# PowerBricksBoard1.net
KiCad netlist of a schematic drawn in EAGLE
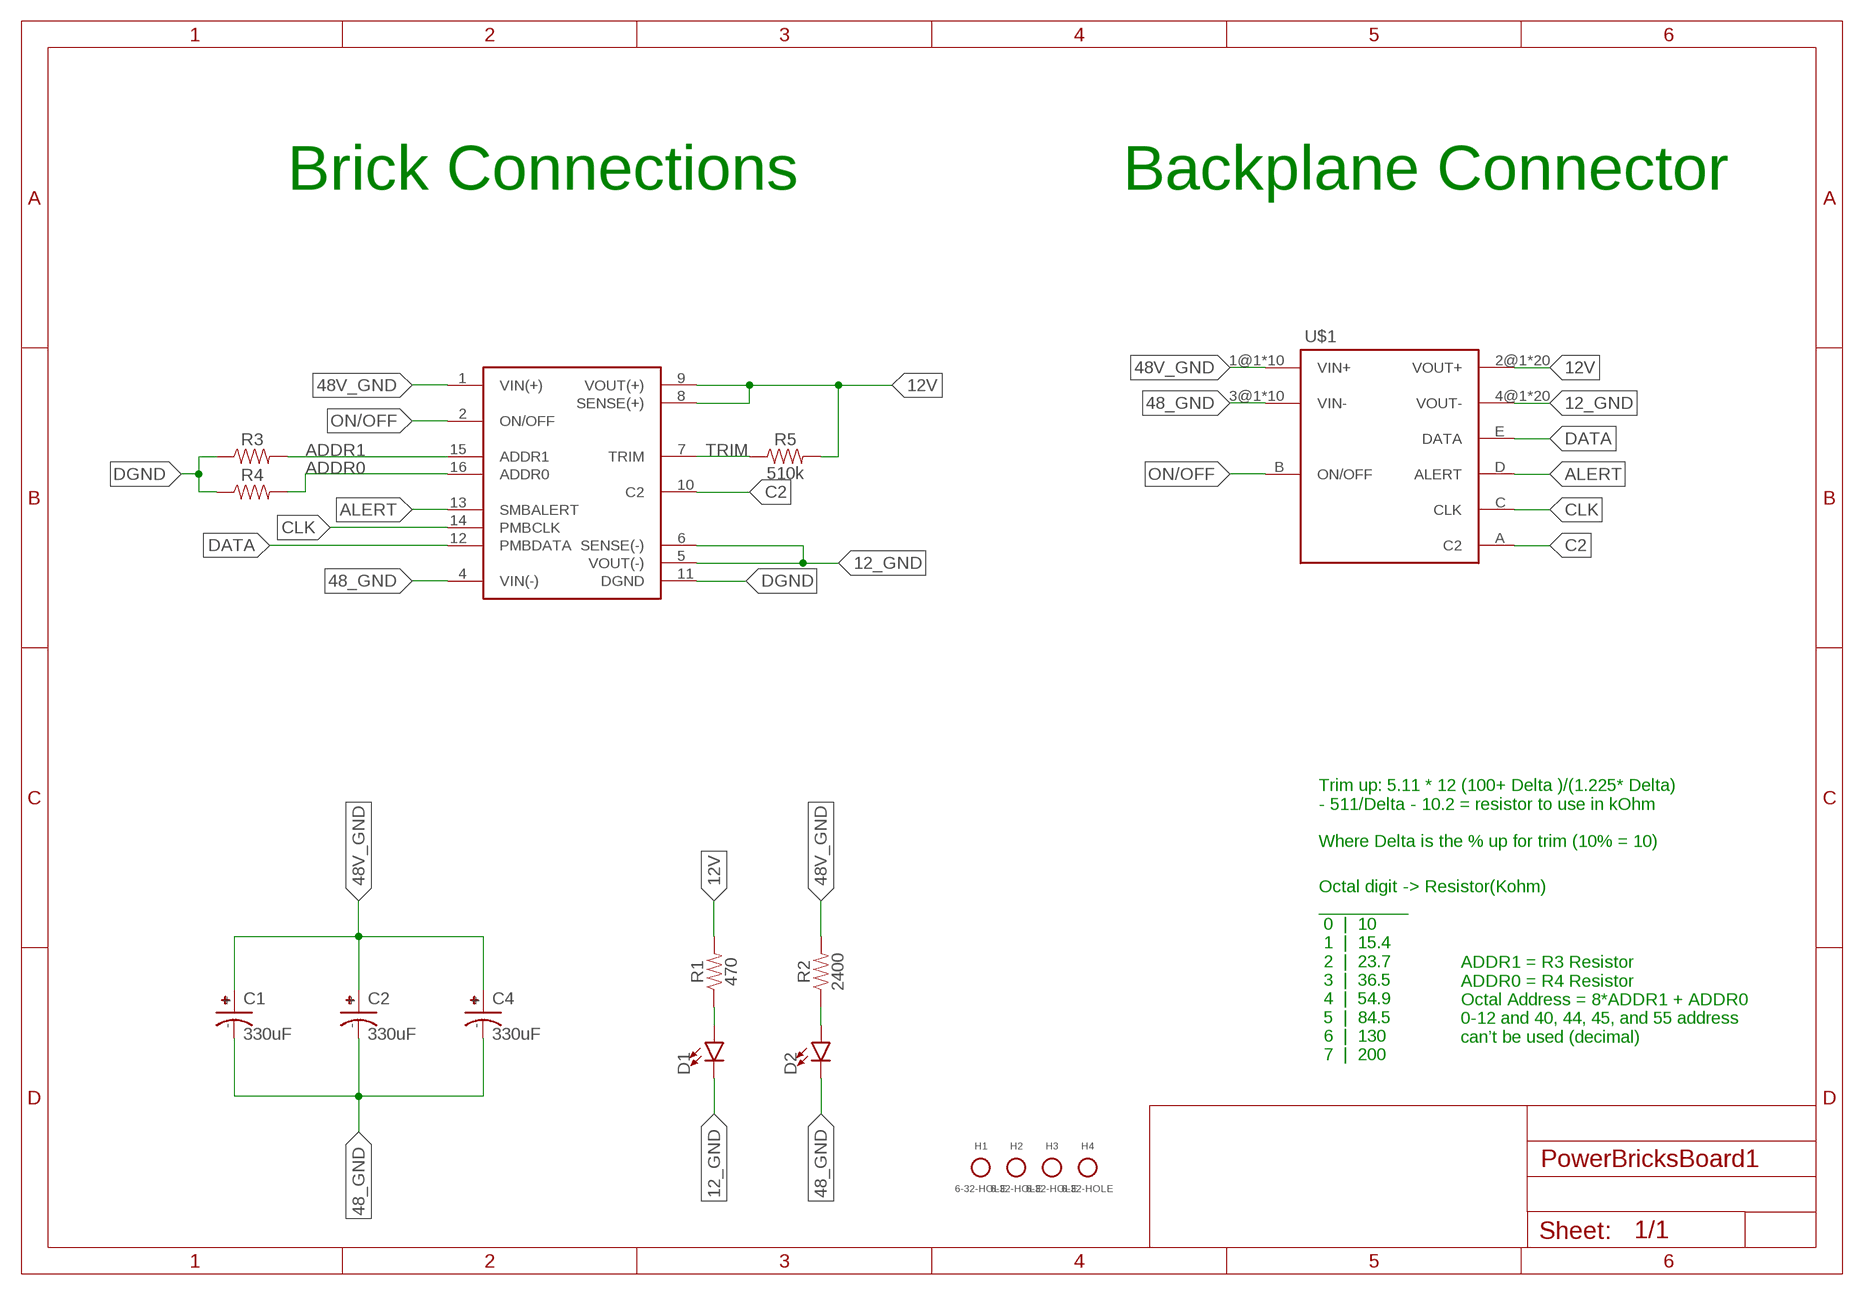
[diagram p0: schematic, sheet 1]

(export (version "E")
  (design (tool "Eeschema 10.0.6"))
  (components
    (comp (ref "C1")
      (value "330uF")
      (footprint "eagle-import:CAPAE1030X1050N")
      (fields
        (field (name "ARROW_PART_NUMBER") "UCM1H331MNL1GS")
        (field (name "MOUSER_PART_NUMBER") "647-UCM1H331MNL1GS")
      )
      (libsource (lib "eagle-import") (part "UCM1H331MNL1GS"))
    )
    (comp (ref "C2")
      (value "330uF")
      (footprint "eagle-import:CAPAE1030X1050N")
      (fields
        (field (name "ARROW_PART_NUMBER") "UCM1H331MNL1GS")
        (field (name "MOUSER_PART_NUMBER") "647-UCM1H331MNL1GS")
      )
      (libsource (lib "eagle-import") (part "UCM1H331MNL1GS"))
    )
    (comp (ref "C4")
      (value "330uF")
      (footprint "eagle-import:CAPAE1030X1050N")
      (fields
        (field (name "ARROW_PART_NUMBER") "UCM1H331MNL1GS")
        (field (name "MOUSER_PART_NUMBER") "647-UCM1H331MNL1GS")
      )
      (libsource (lib "eagle-import") (part "UCM1H331MNL1GS"))
    )
    (comp (ref "D1")
      (value "LED0603")
      (footprint "eagle-import:LED-0603")
      (libsource (lib "eagle-import") (part "LED0603"))
    )
    (comp (ref "D2")
      (value "LED0603")
      (footprint "eagle-import:LED-0603")
      (libsource (lib "eagle-import") (part "LED0603"))
    )
    (comp (ref "H1")
      (value "6-32-HOLE")
      (footprint "eagle-import:6-32-HOLE")
      (libsource (lib "eagle-import") (part "6-32-HOLE"))
    )
    (comp (ref "H2")
      (value "6-32-HOLE")
      (footprint "eagle-import:6-32-HOLE")
      (libsource (lib "eagle-import") (part "6-32-HOLE"))
    )
    (comp (ref "H3")
      (value "6-32-HOLE")
      (footprint "eagle-import:6-32-HOLE")
      (libsource (lib "eagle-import") (part "6-32-HOLE"))
    )
    (comp (ref "H4")
      (value "6-32-HOLE")
      (footprint "eagle-import:6-32-HOLE")
      (libsource (lib "eagle-import") (part "6-32-HOLE"))
    )
    (comp (ref "R1")
      (value "470")
      (footprint "eagle-import:0603")
      (libsource (lib "eagle-import") (part "RESISTOR0603"))
    )
    (comp (ref "R2")
      (value "2400")
      (footprint "eagle-import:0603")
      (libsource (lib "eagle-import") (part "RESISTOR0603"))
    )
    (comp (ref "R3")
      (value "RESISTOR0603")
      (footprint "eagle-import:0603")
      (libsource (lib "eagle-import") (part "RESISTOR0603"))
    )
    (comp (ref "R4")
      (value "RESISTOR0603")
      (footprint "eagle-import:0603")
      (libsource (lib "eagle-import") (part "RESISTOR0603"))
    )
    (comp (ref "R5")
      (value "510k")
      (footprint "eagle-import:0603")
      (libsource (lib "eagle-import") (part "RESISTOR0603"))
    )
    (comp (ref "U$1")
      (value "BRICK2DIST")
      (footprint "eagle-import:BRICK2DIST_D2")
      (libsource (lib "eagle-import") (part "BRICK2DIST"))
    )
    (comp (ref "U$2")
      (value "Q48SC12050NRDH")
      (footprint "eagle-import:Q48SC12050NRDH")
      (libsource (lib "eagle-import") (part "Q48SC12050NRDH"))
    )
  )
  (nets
    (net (code "1") (name "/ADDR0") (class "Default")
      (node (ref "R4") (pin "2") (pinfunction "2_2") (pintype "passive"))
      (node (ref "U$2") (pin "16") (pinfunction "ADDR0_16") (pintype "bidirectional"))
    )
    (net (code "2") (name "/ADDR1") (class "Default")
      (node (ref "R3") (pin "2") (pinfunction "2_2") (pintype "passive"))
      (node (ref "U$2") (pin "15") (pinfunction "ADDR1_15") (pintype "bidirectional"))
    )
    (net (code "3") (name "/TRIM") (class "Default")
      (node (ref "R5") (pin "1") (pinfunction "1_1") (pintype "passive"))
      (node (ref "U$2") (pin "7") (pinfunction "TRIM_7") (pintype "bidirectional"))
    )
    (net (code "4") (name "12V") (class "Default")
      (node (ref "R1") (pin "2") (pinfunction "2_2") (pintype "passive"))
      (node (ref "R5") (pin "2") (pinfunction "2_2") (pintype "passive"))
      (node (ref "U$1") (pin "2@1") (pinfunction "VOUT+_2@1") (pintype "bidirectional"))
      (node (ref "U$1") (pin "2@10") (pinfunction "VOUT+_2@10") (pintype "bidirectional"))
      (node (ref "U$1") (pin "2@11") (pinfunction "VOUT+_2@11") (pintype "bidirectional"))
      (node (ref "U$1") (pin "2@12") (pinfunction "VOUT+_2@12") (pintype "bidirectional"))
      (node (ref "U$1") (pin "2@13") (pinfunction "VOUT+_2@13") (pintype "bidirectional"))
      (node (ref "U$1") (pin "2@14") (pinfunction "VOUT+_2@14") (pintype "bidirectional"))
      (node (ref "U$1") (pin "2@15") (pinfunction "VOUT+_2@15") (pintype "bidirectional"))
      (node (ref "U$1") (pin "2@16") (pinfunction "VOUT+_2@16") (pintype "bidirectional"))
      (node (ref "U$1") (pin "2@17") (pinfunction "VOUT+_2@17") (pintype "bidirectional"))
      (node (ref "U$1") (pin "2@18") (pinfunction "VOUT+_2@18") (pintype "bidirectional"))
      (node (ref "U$1") (pin "2@19") (pinfunction "VOUT+_2@19") (pintype "bidirectional"))
      (node (ref "U$1") (pin "2@2") (pinfunction "VOUT+_2@2") (pintype "bidirectional"))
      (node (ref "U$1") (pin "2@20") (pinfunction "VOUT+_2@20") (pintype "bidirectional"))
      (node (ref "U$1") (pin "2@3") (pinfunction "VOUT+_2@3") (pintype "bidirectional"))
      (node (ref "U$1") (pin "2@4") (pinfunction "VOUT+_2@4") (pintype "bidirectional"))
      (node (ref "U$1") (pin "2@5") (pinfunction "VOUT+_2@5") (pintype "bidirectional"))
      (node (ref "U$1") (pin "2@6") (pinfunction "VOUT+_2@6") (pintype "bidirectional"))
      (node (ref "U$1") (pin "2@7") (pinfunction "VOUT+_2@7") (pintype "bidirectional"))
      (node (ref "U$1") (pin "2@8") (pinfunction "VOUT+_2@8") (pintype "bidirectional"))
      (node (ref "U$1") (pin "2@9") (pinfunction "VOUT+_2@9") (pintype "bidirectional"))
      (node (ref "U$2") (pin "8") (pinfunction "SENSE(+)_8") (pintype "bidirectional"))
      (node (ref "U$2") (pin "9") (pinfunction "VOUT(+)_9") (pintype "bidirectional"))
    )
    (net (code "5") (name "12_GND") (class "Default")
      (node (ref "D1") (pin "C") (pinfunction "C_C") (pintype "passive"))
      (node (ref "U$1") (pin "4@1") (pinfunction "VOUT-_4@1") (pintype "bidirectional"))
      (node (ref "U$1") (pin "4@10") (pinfunction "VOUT-_4@10") (pintype "bidirectional"))
      (node (ref "U$1") (pin "4@11") (pinfunction "VOUT-_4@11") (pintype "bidirectional"))
      (node (ref "U$1") (pin "4@12") (pinfunction "VOUT-_4@12") (pintype "bidirectional"))
      (node (ref "U$1") (pin "4@13") (pinfunction "VOUT-_4@13") (pintype "bidirectional"))
      (node (ref "U$1") (pin "4@14") (pinfunction "VOUT-_4@14") (pintype "bidirectional"))
      (node (ref "U$1") (pin "4@15") (pinfunction "VOUT-_4@15") (pintype "bidirectional"))
      (node (ref "U$1") (pin "4@16") (pinfunction "VOUT-_4@16") (pintype "bidirectional"))
      (node (ref "U$1") (pin "4@17") (pinfunction "VOUT-_4@17") (pintype "bidirectional"))
      (node (ref "U$1") (pin "4@18") (pinfunction "VOUT-_4@18") (pintype "bidirectional"))
      (node (ref "U$1") (pin "4@19") (pinfunction "VOUT-_4@19") (pintype "bidirectional"))
      (node (ref "U$1") (pin "4@2") (pinfunction "VOUT-_4@2") (pintype "bidirectional"))
      (node (ref "U$1") (pin "4@20") (pinfunction "VOUT-_4@20") (pintype "bidirectional"))
      (node (ref "U$1") (pin "4@3") (pinfunction "VOUT-_4@3") (pintype "bidirectional"))
      (node (ref "U$1") (pin "4@4") (pinfunction "VOUT-_4@4") (pintype "bidirectional"))
      (node (ref "U$1") (pin "4@5") (pinfunction "VOUT-_4@5") (pintype "bidirectional"))
      (node (ref "U$1") (pin "4@6") (pinfunction "VOUT-_4@6") (pintype "bidirectional"))
      (node (ref "U$1") (pin "4@7") (pinfunction "VOUT-_4@7") (pintype "bidirectional"))
      (node (ref "U$1") (pin "4@8") (pinfunction "VOUT-_4@8") (pintype "bidirectional"))
      (node (ref "U$1") (pin "4@9") (pinfunction "VOUT-_4@9") (pintype "bidirectional"))
      (node (ref "U$2") (pin "5") (pinfunction "VOUT(-)_5") (pintype "bidirectional"))
      (node (ref "U$2") (pin "6") (pinfunction "SENSE(-)_6") (pintype "bidirectional"))
    )
    (net (code "6") (name "48V_GND") (class "Default")
      (node (ref "C1") (pin "+") (pinfunction "+_+") (pintype "bidirectional"))
      (node (ref "C2") (pin "+") (pinfunction "+_+") (pintype "bidirectional"))
      (node (ref "C4") (pin "+") (pinfunction "+_+") (pintype "bidirectional"))
      (node (ref "R2") (pin "2") (pinfunction "2_2") (pintype "passive"))
      (node (ref "U$1") (pin "1@1") (pinfunction "VIN+_1@1") (pintype "bidirectional"))
      (node (ref "U$1") (pin "1@10") (pinfunction "VIN+_1@10") (pintype "bidirectional"))
      (node (ref "U$1") (pin "1@2") (pinfunction "VIN+_1@2") (pintype "bidirectional"))
      (node (ref "U$1") (pin "1@3") (pinfunction "VIN+_1@3") (pintype "bidirectional"))
      (node (ref "U$1") (pin "1@4") (pinfunction "VIN+_1@4") (pintype "bidirectional"))
      (node (ref "U$1") (pin "1@5") (pinfunction "VIN+_1@5") (pintype "bidirectional"))
      (node (ref "U$1") (pin "1@6") (pinfunction "VIN+_1@6") (pintype "bidirectional"))
      (node (ref "U$1") (pin "1@7") (pinfunction "VIN+_1@7") (pintype "bidirectional"))
      (node (ref "U$1") (pin "1@8") (pinfunction "VIN+_1@8") (pintype "bidirectional"))
      (node (ref "U$1") (pin "1@9") (pinfunction "VIN+_1@9") (pintype "bidirectional"))
      (node (ref "U$2") (pin "1") (pinfunction "VIN(+)_1") (pintype "bidirectional"))
    )
    (net (code "7") (name "48_GND") (class "Default")
      (node (ref "C1") (pin "-") (pinfunction "-_-") (pintype "bidirectional"))
      (node (ref "C2") (pin "-") (pinfunction "-_-") (pintype "bidirectional"))
      (node (ref "C4") (pin "-") (pinfunction "-_-") (pintype "bidirectional"))
      (node (ref "D2") (pin "C") (pinfunction "C_C") (pintype "passive"))
      (node (ref "U$1") (pin "3@1") (pinfunction "VIN-_3@1") (pintype "bidirectional"))
      (node (ref "U$1") (pin "3@10") (pinfunction "VIN-_3@10") (pintype "bidirectional"))
      (node (ref "U$1") (pin "3@2") (pinfunction "VIN-_3@2") (pintype "bidirectional"))
      (node (ref "U$1") (pin "3@3") (pinfunction "VIN-_3@3") (pintype "bidirectional"))
      (node (ref "U$1") (pin "3@4") (pinfunction "VIN-_3@4") (pintype "bidirectional"))
      (node (ref "U$1") (pin "3@5") (pinfunction "VIN-_3@5") (pintype "bidirectional"))
      (node (ref "U$1") (pin "3@6") (pinfunction "VIN-_3@6") (pintype "bidirectional"))
      (node (ref "U$1") (pin "3@7") (pinfunction "VIN-_3@7") (pintype "bidirectional"))
      (node (ref "U$1") (pin "3@8") (pinfunction "VIN-_3@8") (pintype "bidirectional"))
      (node (ref "U$1") (pin "3@9") (pinfunction "VIN-_3@9") (pintype "bidirectional"))
      (node (ref "U$2") (pin "4") (pinfunction "VIN(-)_4") (pintype "bidirectional"))
    )
    (net (code "8") (name "ALERT") (class "Default")
      (node (ref "U$1") (pin "D") (pinfunction "ALERT_D") (pintype "bidirectional"))
      (node (ref "U$2") (pin "13") (pinfunction "SMBALERT_13") (pintype "bidirectional"))
    )
    (net (code "9") (name "C2") (class "Default")
      (node (ref "U$1") (pin "A") (pinfunction "C2_A") (pintype "bidirectional"))
      (node (ref "U$2") (pin "10") (pinfunction "C2_10") (pintype "bidirectional"))
    )
    (net (code "10") (name "CLK") (class "Default")
      (node (ref "U$1") (pin "C") (pinfunction "CLK_C") (pintype "bidirectional"))
      (node (ref "U$2") (pin "14") (pinfunction "PMBCLK_14") (pintype "bidirectional"))
    )
    (net (code "11") (name "DATA") (class "Default")
      (node (ref "U$1") (pin "E") (pinfunction "DATA_E") (pintype "bidirectional"))
      (node (ref "U$2") (pin "12") (pinfunction "PMBDATA_12") (pintype "bidirectional"))
    )
    (net (code "12") (name "DGND") (class "Default")
      (node (ref "R3") (pin "1") (pinfunction "1_1") (pintype "passive"))
      (node (ref "R4") (pin "1") (pinfunction "1_1") (pintype "passive"))
      (node (ref "U$2") (pin "11") (pinfunction "DGND_11") (pintype "bidirectional"))
    )
    (net (code "13") (name "Net-(D1-PadA)") (class "Default")
      (node (ref "D1") (pin "A") (pinfunction "A_A") (pintype "passive"))
      (node (ref "R1") (pin "1") (pinfunction "1_1") (pintype "passive"))
    )
    (net (code "14") (name "Net-(D2-PadA)") (class "Default")
      (node (ref "D2") (pin "A") (pinfunction "A_A") (pintype "passive"))
      (node (ref "R2") (pin "1") (pinfunction "1_1") (pintype "passive"))
    )
    (net (code "15") (name "ON{slash}OFF") (class "Default")
      (node (ref "U$1") (pin "B") (pinfunction "ON/OFF_B") (pintype "bidirectional"))
      (node (ref "U$2") (pin "2") (pinfunction "ON/OFF_2") (pintype "bidirectional"))
    )
  )
)
